# Cap-Sense-PCB.net
KiCad netlist of a schematic drawn in EAGLE
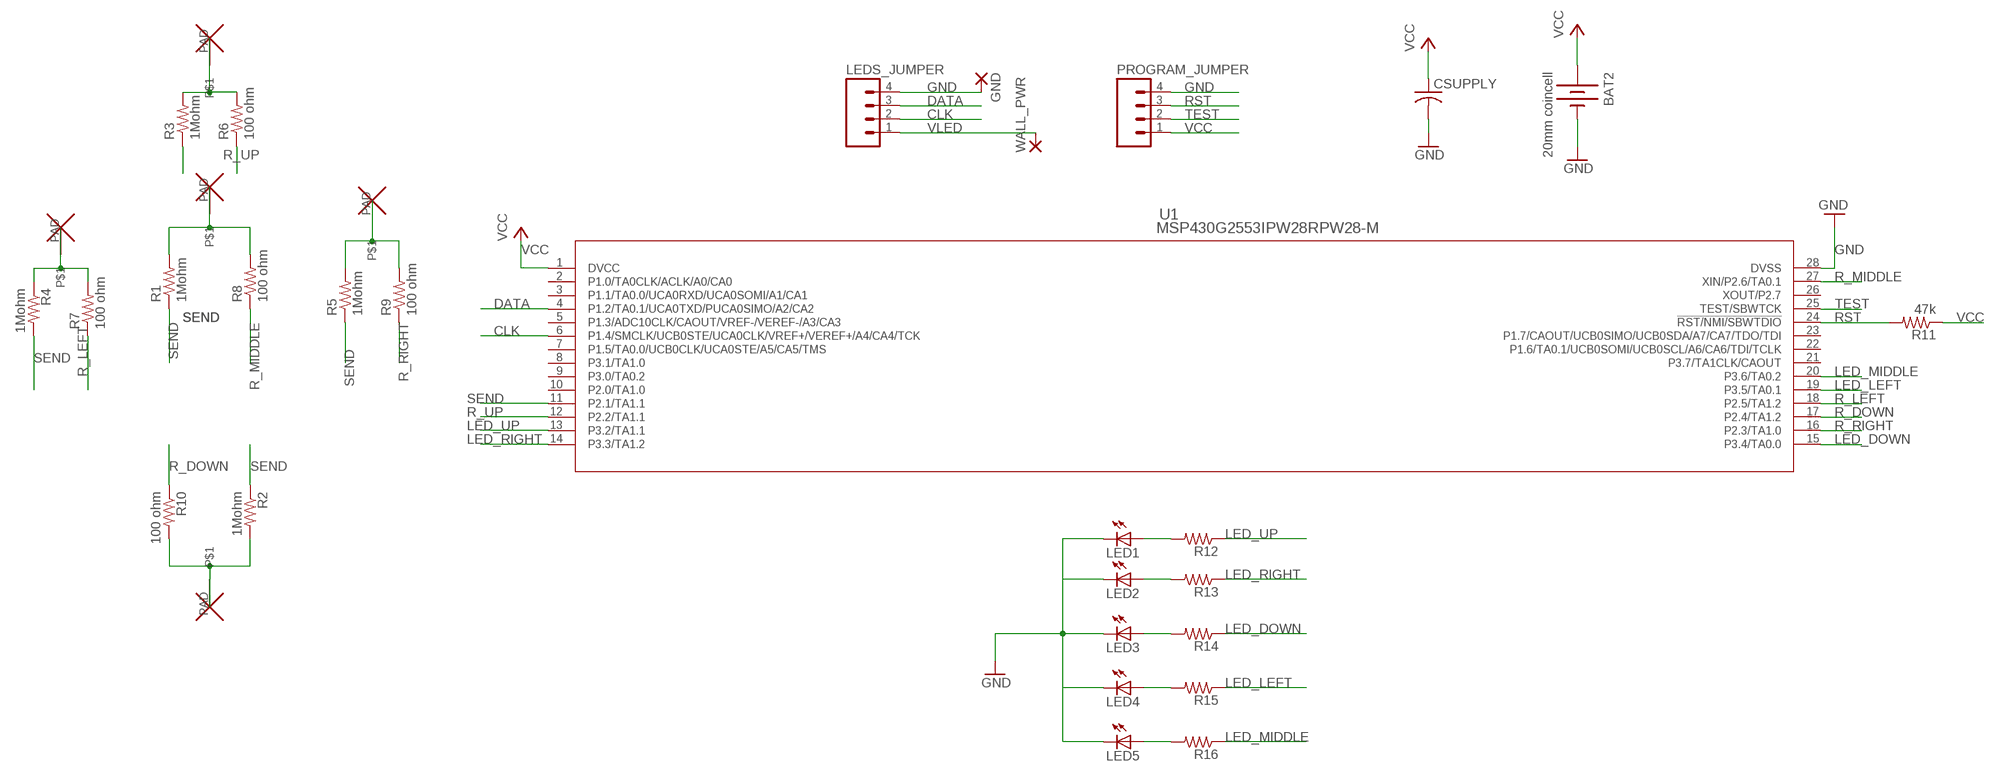
[diagram p0: schematic, sheet 1]

(export (version "E")
  (design (tool "Eeschema 10.0.6"))
  (components
    (comp (ref "BAT2")
      (value "20mm coincell")
      (footprint "eagle-import:BATTCON_20MM_PTH_COMPACT")
      (libsource (lib "eagle-import") (part "BATTERYFOB"))
    )
    (comp (ref "CSUPPLY")
      (value "C-USC1206")
      (footprint "eagle-import:C1206")
      (libsource (lib "eagle-import") (part "C-USC1206"))
    )
    (comp (ref "DOWN")
      (value "KAP_PAD")
      (footprint "eagle-import:KAP_PAD")
      (libsource (lib "eagle-import") (part "KAP_PAD"))
    )
    (comp (ref "GND")
      (value "SMD5")
      (footprint "eagle-import:SMD2,54-5,08")
      (libsource (lib "eagle-import") (part "SMD5"))
    )
    (comp (ref "LED1")
      (value "LEDCHIPLED_1206")
      (footprint "eagle-import:CHIPLED_1206")
      (libsource (lib "eagle-import") (part "LEDCHIPLED_1206"))
    )
    (comp (ref "LED2")
      (value "LEDCHIPLED_1206")
      (footprint "eagle-import:CHIPLED_1206")
      (libsource (lib "eagle-import") (part "LEDCHIPLED_1206"))
    )
    (comp (ref "LED3")
      (value "LEDCHIPLED_1206")
      (footprint "eagle-import:CHIPLED_1206")
      (libsource (lib "eagle-import") (part "LEDCHIPLED_1206"))
    )
    (comp (ref "LED4")
      (value "LEDCHIPLED_1206")
      (footprint "eagle-import:CHIPLED_1206")
      (libsource (lib "eagle-import") (part "LEDCHIPLED_1206"))
    )
    (comp (ref "LED5")
      (value "LEDCHIPLED_1206")
      (footprint "eagle-import:CHIPLED_1206")
      (libsource (lib "eagle-import") (part "LEDCHIPLED_1206"))
    )
    (comp (ref "LEDS_JUMPER")
      (value "M04LOCK")
      (footprint "eagle-import:1X04_LOCK")
      (libsource (lib "eagle-import") (part "M04LOCK"))
    )
    (comp (ref "LEFT")
      (value "KAP_PAD")
      (footprint "eagle-import:KAP_PAD")
      (libsource (lib "eagle-import") (part "KAP_PAD"))
    )
    (comp (ref "MIDDLE")
      (value "KAP_PAD")
      (footprint "eagle-import:KAP_PAD")
      (libsource (lib "eagle-import") (part "KAP_PAD"))
    )
    (comp (ref "PROGRAM_JUMPER")
      (value "M04LOCK")
      (footprint "eagle-import:1X04_LOCK")
      (libsource (lib "eagle-import") (part "M04LOCK"))
    )
    (comp (ref "R1")
      (value "1Mohm")
      (footprint "eagle-import:R1206")
      (libsource (lib "eagle-import") (part "R-US_R1206"))
    )
    (comp (ref "R2")
      (value "1Mohm")
      (footprint "eagle-import:R1206")
      (libsource (lib "eagle-import") (part "R-US_R1206"))
    )
    (comp (ref "R3")
      (value "1Mohm")
      (footprint "eagle-import:R1206")
      (libsource (lib "eagle-import") (part "R-US_R1206"))
    )
    (comp (ref "R4")
      (value "1Mohm")
      (footprint "eagle-import:R1206")
      (libsource (lib "eagle-import") (part "R-US_R1206"))
    )
    (comp (ref "R5")
      (value "1Mohm")
      (footprint "eagle-import:R1206")
      (libsource (lib "eagle-import") (part "R-US_R1206"))
    )
    (comp (ref "R6")
      (value "100 ohm")
      (footprint "eagle-import:R1206")
      (libsource (lib "eagle-import") (part "R-US_R1206"))
    )
    (comp (ref "R7")
      (value "100 ohm")
      (footprint "eagle-import:R1206")
      (libsource (lib "eagle-import") (part "R-US_R1206"))
    )
    (comp (ref "R8")
      (value "100 ohm")
      (footprint "eagle-import:R1206")
      (libsource (lib "eagle-import") (part "R-US_R1206"))
    )
    (comp (ref "R9")
      (value "100 ohm")
      (footprint "eagle-import:R1206")
      (libsource (lib "eagle-import") (part "R-US_R1206"))
    )
    (comp (ref "R10")
      (value "100 ohm")
      (footprint "eagle-import:R1206")
      (libsource (lib "eagle-import") (part "R-US_R1206"))
    )
    (comp (ref "R11")
      (value "47k")
      (footprint "eagle-import:R1206")
      (libsource (lib "eagle-import") (part "R-US_R1206"))
    )
    (comp (ref "R12")
      (value "R-US_R1206")
      (footprint "eagle-import:R1206")
      (libsource (lib "eagle-import") (part "rcl_334_R-US_R1206"))
    )
    (comp (ref "R13")
      (value "R-US_R1206")
      (footprint "eagle-import:R1206")
      (libsource (lib "eagle-import") (part "rcl_334_R-US_R1206"))
    )
    (comp (ref "R14")
      (value "R-US_R1206")
      (footprint "eagle-import:R1206")
      (libsource (lib "eagle-import") (part "rcl_334_R-US_R1206"))
    )
    (comp (ref "R15")
      (value "R-US_R1206")
      (footprint "eagle-import:R1206")
      (libsource (lib "eagle-import") (part "rcl_334_R-US_R1206"))
    )
    (comp (ref "R16")
      (value "R-US_R1206")
      (footprint "eagle-import:R1206")
      (libsource (lib "eagle-import") (part "rcl_334_R-US_R1206"))
    )
    (comp (ref "RIGHT")
      (value "KAP_PAD")
      (footprint "eagle-import:KAP_PAD")
      (libsource (lib "eagle-import") (part "KAP_PAD"))
    )
    (comp (ref "U1")
      (value "MSP430G2553IPW28RPW28-M")
      (footprint "eagle-import:PW28-M")
      (fields (field (name "MANUFACTURER_PART_NUMBER") "MSP430G2553IPW28R"))
      (libsource (lib "eagle-import") (part "MSP430G2553IPW28RPW28-M"))
    )
    (comp (ref "UP")
      (value "KAP_PAD")
      (footprint "eagle-import:KAP_PAD")
      (libsource (lib "eagle-import") (part "KAP_PAD"))
    )
    (comp (ref "WALL_PWR")
      (value "SMD5")
      (footprint "eagle-import:SMD2,54-5,08")
      (libsource (lib "eagle-import") (part "SMD5"))
    )
  )
  (nets
    (net (code "1") (name "/CLK") (class "Default")
      (node (ref "LEDS_JUMPER") (pin "2") (pinfunction "2_2") (pintype "passive"))
      (node (ref "U1") (pin "6") (pinfunction "P1.4/SMCLK/UCB0STE/UCA0CLK/VREF+/VEREF+/A4/CA4/TCK_6") (pintype "bidirectional"))
    )
    (net (code "2") (name "/DATA") (class "Default")
      (node (ref "LEDS_JUMPER") (pin "3") (pinfunction "3_3") (pintype "passive"))
      (node (ref "U1") (pin "4") (pinfunction "P1.2/TA0.1/UCA0TXD/PUCA0SIMO/A2/CA2_4") (pintype "bidirectional"))
    )
    (net (code "3") (name "/LED_DOWN") (class "Default")
      (node (ref "R14") (pin "1") (pinfunction "1_1") (pintype "passive"))
      (node (ref "U1") (pin "15") (pinfunction "P3.4/TA0.0_15") (pintype "bidirectional"))
    )
    (net (code "4") (name "/LED_LEFT") (class "Default")
      (node (ref "R15") (pin "1") (pinfunction "1_1") (pintype "passive"))
      (node (ref "U1") (pin "19") (pinfunction "P3.5/TA0.1_19") (pintype "bidirectional"))
    )
    (net (code "5") (name "/LED_MIDDLE") (class "Default")
      (node (ref "R16") (pin "1") (pinfunction "1_1") (pintype "passive"))
      (node (ref "U1") (pin "20") (pinfunction "P3.6/TA0.2_20") (pintype "bidirectional"))
    )
    (net (code "6") (name "/LED_RIGHT") (class "Default")
      (node (ref "R13") (pin "1") (pinfunction "1_1") (pintype "passive"))
      (node (ref "U1") (pin "14") (pinfunction "P3.3/TA1.2_14") (pintype "bidirectional"))
    )
    (net (code "7") (name "/LED_UP") (class "Default")
      (node (ref "R12") (pin "1") (pinfunction "1_1") (pintype "passive"))
      (node (ref "U1") (pin "13") (pinfunction "P3.2/TA1.1_13") (pintype "bidirectional"))
    )
    (net (code "8") (name "/RST") (class "Default")
      (node (ref "PROGRAM_JUMPER") (pin "3") (pinfunction "3_3") (pintype "passive"))
      (node (ref "R11") (pin "2") (pinfunction "2_2") (pintype "passive"))
      (node (ref "U1") (pin "24") (pinfunction "~{RST/NMI/SBWTDIO}_24") (pintype "bidirectional"))
    )
    (net (code "9") (name "/R_DOWN") (class "Default")
      (node (ref "R10") (pin "1") (pinfunction "1_1") (pintype "passive"))
      (node (ref "U1") (pin "17") (pinfunction "P2.4/TA1.2_17") (pintype "bidirectional"))
    )
    (net (code "10") (name "/R_LEFT") (class "Default")
      (node (ref "R7") (pin "1") (pinfunction "1_1") (pintype "passive"))
      (node (ref "U1") (pin "18") (pinfunction "P2.5/TA1.2_18") (pintype "bidirectional"))
    )
    (net (code "11") (name "/R_MIDDLE") (class "Default")
      (node (ref "R8") (pin "1") (pinfunction "1_1") (pintype "passive"))
      (node (ref "U1") (pin "27") (pinfunction "XIN/P2.6/TA0.1_27") (pintype "bidirectional"))
    )
    (net (code "12") (name "/R_RIGHT") (class "Default")
      (node (ref "R9") (pin "1") (pinfunction "1_1") (pintype "passive"))
      (node (ref "U1") (pin "16") (pinfunction "P2.3/TA1.0_16") (pintype "bidirectional"))
    )
    (net (code "13") (name "/R_UP") (class "Default")
      (node (ref "R6") (pin "1") (pinfunction "1_1") (pintype "passive"))
      (node (ref "U1") (pin "12") (pinfunction "P2.2/TA1.1_12") (pintype "bidirectional"))
    )
    (net (code "14") (name "/SEND") (class "Default")
      (node (ref "R1") (pin "1") (pinfunction "1_1") (pintype "passive"))
      (node (ref "R2") (pin "1") (pinfunction "1_1") (pintype "passive"))
      (node (ref "R3") (pin "1") (pinfunction "1_1") (pintype "passive"))
      (node (ref "R4") (pin "2") (pinfunction "2_2") (pintype "passive"))
      (node (ref "R5") (pin "1") (pinfunction "1_1") (pintype "passive"))
      (node (ref "U1") (pin "11") (pinfunction "P2.1/TA1.1_11") (pintype "bidirectional"))
    )
    (net (code "15") (name "/TEST") (class "Default")
      (node (ref "PROGRAM_JUMPER") (pin "2") (pinfunction "2_2") (pintype "passive"))
      (node (ref "U1") (pin "25") (pinfunction "TEST/SBWTCK_25") (pintype "bidirectional"))
    )
    (net (code "16") (name "/VLED") (class "Default")
      (node (ref "LEDS_JUMPER") (pin "1") (pinfunction "1_1") (pintype "passive"))
      (node (ref "WALL_PWR") (pin "1") (pinfunction "P_1") (pintype "passive"))
    )
    (net (code "17") (name "GND") (class "Default")
      (node (ref "BAT2") (pin "2") (pinfunction "-_2") (pintype "power_in"))
      (node (ref "CSUPPLY") (pin "2") (pinfunction "2_2") (pintype "passive"))
      (node (ref "GND") (pin "1") (pinfunction "P_1") (pintype "passive"))
      (node (ref "LED1") (pin "C") (pinfunction "C_C") (pintype "passive"))
      (node (ref "LED2") (pin "C") (pinfunction "C_C") (pintype "passive"))
      (node (ref "LED3") (pin "C") (pinfunction "C_C") (pintype "passive"))
      (node (ref "LED4") (pin "C") (pinfunction "C_C") (pintype "passive"))
      (node (ref "LED5") (pin "C") (pinfunction "C_C") (pintype "passive"))
      (node (ref "LEDS_JUMPER") (pin "4") (pinfunction "4_4") (pintype "passive"))
      (node (ref "PROGRAM_JUMPER") (pin "4") (pinfunction "4_4") (pintype "passive"))
      (node (ref "U1") (pin "28") (pinfunction "DVSS_28") (pintype "power_in"))
    )
    (net (code "18") (name "Net-(DOWN-P$1)") (class "Default")
      (node (ref "DOWN") (pin "PAD") (pinfunction "P$1_PAD") (pintype "bidirectional"))
      (node (ref "R10") (pin "2") (pinfunction "2_2") (pintype "passive"))
      (node (ref "R2") (pin "2") (pinfunction "2_2") (pintype "passive"))
    )
    (net (code "19") (name "Net-(LED1-PadA)") (class "Default")
      (node (ref "LED1") (pin "A") (pinfunction "A_A") (pintype "passive"))
      (node (ref "R12") (pin "2") (pinfunction "2_2") (pintype "passive"))
    )
    (net (code "20") (name "Net-(LED2-PadA)") (class "Default")
      (node (ref "LED2") (pin "A") (pinfunction "A_A") (pintype "passive"))
      (node (ref "R13") (pin "2") (pinfunction "2_2") (pintype "passive"))
    )
    (net (code "21") (name "Net-(LED3-PadA)") (class "Default")
      (node (ref "LED3") (pin "A") (pinfunction "A_A") (pintype "passive"))
      (node (ref "R14") (pin "2") (pinfunction "2_2") (pintype "passive"))
    )
    (net (code "22") (name "Net-(LED4-PadA)") (class "Default")
      (node (ref "LED4") (pin "A") (pinfunction "A_A") (pintype "passive"))
      (node (ref "R15") (pin "2") (pinfunction "2_2") (pintype "passive"))
    )
    (net (code "23") (name "Net-(LED5-PadA)") (class "Default")
      (node (ref "LED5") (pin "A") (pinfunction "A_A") (pintype "passive"))
      (node (ref "R16") (pin "2") (pinfunction "2_2") (pintype "passive"))
    )
    (net (code "24") (name "Net-(LEFT-P$1)") (class "Default")
      (node (ref "LEFT") (pin "PAD") (pinfunction "P$1_PAD") (pintype "bidirectional"))
      (node (ref "R4") (pin "1") (pinfunction "1_1") (pintype "passive"))
      (node (ref "R7") (pin "2") (pinfunction "2_2") (pintype "passive"))
    )
    (net (code "25") (name "Net-(MIDDLE-P$1)") (class "Default")
      (node (ref "MIDDLE") (pin "PAD") (pinfunction "P$1_PAD") (pintype "bidirectional"))
      (node (ref "R1") (pin "2") (pinfunction "2_2") (pintype "passive"))
      (node (ref "R8") (pin "2") (pinfunction "2_2") (pintype "passive"))
    )
    (net (code "26") (name "Net-(RIGHT-P$1)") (class "Default")
      (node (ref "R5") (pin "2") (pinfunction "2_2") (pintype "passive"))
      (node (ref "R9") (pin "2") (pinfunction "2_2") (pintype "passive"))
      (node (ref "RIGHT") (pin "PAD") (pinfunction "P$1_PAD") (pintype "bidirectional"))
    )
    (net (code "27") (name "Net-(UP-P$1)") (class "Default")
      (node (ref "R3") (pin "2") (pinfunction "2_2") (pintype "passive"))
      (node (ref "R6") (pin "2") (pinfunction "2_2") (pintype "passive"))
      (node (ref "UP") (pin "PAD") (pinfunction "P$1_PAD") (pintype "bidirectional"))
    )
    (net (code "28") (name "VCC") (class "Default")
      (node (ref "BAT2") (pin "1") (pinfunction "+_1") (pintype "power_in"))
      (node (ref "BAT2") (pin "3") (pinfunction "+_3") (pintype "power_in"))
      (node (ref "BAT2") (pin "4") (pinfunction "+_4") (pintype "power_in"))
      (node (ref "BAT2") (pin "5") (pinfunction "+_5") (pintype "power_in"))
      (node (ref "CSUPPLY") (pin "1") (pinfunction "1_1") (pintype "passive"))
      (node (ref "PROGRAM_JUMPER") (pin "1") (pinfunction "1_1") (pintype "passive"))
      (node (ref "R11") (pin "1") (pinfunction "1_1") (pintype "passive"))
      (node (ref "U1") (pin "1") (pinfunction "DVCC_1") (pintype "power_in"))
    )
    (net (code "29") (name "unconnected-(U1-P1.0{slash}TA0CLK{slash}ACLK{slash}A0{slash}CA0-Pad2)") (class "Default")
      (node (ref "U1") (pin "2") (pinfunction "P1.0/TA0CLK/ACLK/A0/CA0_2") (pintype "bidirectional"))
    )
    (net (code "30") (name "unconnected-(U1-P1.1{slash}TA0.0{slash}UCA0RXD{slash}UCA0SOMI{slash}A1{slash}CA1-Pad3)") (class "Default")
      (node (ref "U1") (pin "3") (pinfunction "P1.1/TA0.0/UCA0RXD/UCA0SOMI/A1/CA1_3") (pintype "bidirectional"))
    )
    (net (code "31") (name "unconnected-(U1-P1.3{slash}ADC10CLK{slash}CAOUT{slash}VREF-{slash}VEREF-{slash}A3{slash}CA3-Pad5)") (class "Default")
      (node (ref "U1") (pin "5") (pinfunction "P1.3/ADC10CLK/CAOUT/VREF-/VEREF-/A3/CA3_5") (pintype "bidirectional"))
    )
    (net (code "32") (name "unconnected-(U1-P1.5{slash}TA0.0{slash}UCB0CLK{slash}UCA0STE{slash}A5{slash}CA5{slash}TMS-Pad7)") (class "Default")
      (node (ref "U1") (pin "7") (pinfunction "P1.5/TA0.0/UCB0CLK/UCA0STE/A5/CA5/TMS_7") (pintype "bidirectional"))
    )
    (net (code "33") (name "unconnected-(U1-P1.6{slash}TA0.1{slash}UCB0SOMI{slash}UCB0SCL{slash}A6{slash}CA6{slash}TDI{slash}TCLK-Pad22)") (class "Default")
      (node (ref "U1") (pin "22") (pinfunction "P1.6/TA0.1/UCB0SOMI/UCB0SCL/A6/CA6/TDI/TCLK_22") (pintype "bidirectional"))
    )
    (net (code "34") (name "unconnected-(U1-P1.7{slash}CAOUT{slash}UCB0SIMO{slash}UCB0SDA{slash}A7{slash}CA7{slash}TDO{slash}TDI-Pad23)") (class "Default")
      (node (ref "U1") (pin "23") (pinfunction "P1.7/CAOUT/UCB0SIMO/UCB0SDA/A7/CA7/TDO/TDI_23") (pintype "bidirectional"))
    )
    (net (code "35") (name "unconnected-(U1-P2.0{slash}TA1.0-Pad10)") (class "Default")
      (node (ref "U1") (pin "10") (pinfunction "P2.0/TA1.0_10") (pintype "bidirectional"))
    )
    (net (code "36") (name "unconnected-(U1-P3.0{slash}TA0.2-Pad9)") (class "Default")
      (node (ref "U1") (pin "9") (pinfunction "P3.0/TA0.2_9") (pintype "bidirectional"))
    )
    (net (code "37") (name "unconnected-(U1-P3.1{slash}TA1.0-Pad8)") (class "Default")
      (node (ref "U1") (pin "8") (pinfunction "P3.1/TA1.0_8") (pintype "bidirectional"))
    )
    (net (code "38") (name "unconnected-(U1-P3.7{slash}TA1CLK{slash}CAOUT-Pad21)") (class "Default")
      (node (ref "U1") (pin "21") (pinfunction "P3.7/TA1CLK/CAOUT_21") (pintype "bidirectional"))
    )
    (net (code "39") (name "unconnected-(U1-XOUT{slash}P2.7-Pad26)") (class "Default")
      (node (ref "U1") (pin "26") (pinfunction "XOUT/P2.7_26") (pintype "bidirectional"))
    )
  )
)
